# GPIO_SchematicMk2.net
KiCad netlist of a schematic drawn in EAGLE
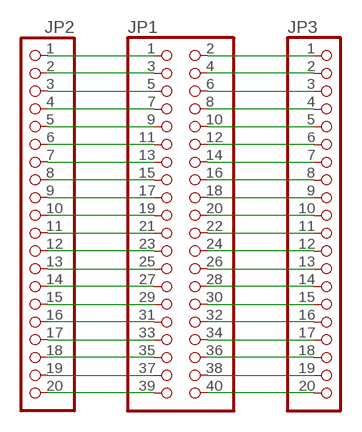
[diagram p0: schematic, sheet 1]

(export (version "E")
  (design (tool "Eeschema 10.0.6"))
  (components
    (comp (ref "JP1")
      (value "PINHD-2X20")
      (footprint "eagle-import:2X20")
      (libsource (lib "eagle-import") (part "PINHD-2X20"))
    )
    (comp (ref "JP2")
      (value "PINHD-1X20")
      (footprint "eagle-import:1X20")
      (libsource (lib "eagle-import") (part "PINHD-1X20"))
    )
    (comp (ref "JP3")
      (value "PINHD-1X20")
      (footprint "eagle-import:1X20")
      (libsource (lib "eagle-import") (part "PINHD-1X20"))
    )
  )
  (nets
    (net (code "1") (name "Net-(JP1-Pad1)") (class "Default")
      (node (ref "JP1") (pin "1") (pinfunction "1_1") (pintype "passive"))
      (node (ref "JP2") (pin "1") (pinfunction "1_1") (pintype "passive"))
    )
    (net (code "2") (name "Net-(JP1-Pad2)") (class "Default")
      (node (ref "JP1") (pin "2") (pinfunction "2_2") (pintype "passive"))
      (node (ref "JP3") (pin "1") (pinfunction "1_1") (pintype "passive"))
    )
    (net (code "3") (name "Net-(JP1-Pad3)") (class "Default")
      (node (ref "JP1") (pin "3") (pinfunction "3_3") (pintype "passive"))
      (node (ref "JP2") (pin "2") (pinfunction "2_2") (pintype "passive"))
    )
    (net (code "4") (name "Net-(JP1-Pad4)") (class "Default")
      (node (ref "JP1") (pin "4") (pinfunction "4_4") (pintype "passive"))
      (node (ref "JP3") (pin "2") (pinfunction "2_2") (pintype "passive"))
    )
    (net (code "5") (name "Net-(JP1-Pad5)") (class "Default")
      (node (ref "JP1") (pin "5") (pinfunction "5_5") (pintype "passive"))
      (node (ref "JP2") (pin "3") (pinfunction "3_3") (pintype "passive"))
    )
    (net (code "6") (name "Net-(JP1-Pad6)") (class "Default")
      (node (ref "JP1") (pin "6") (pinfunction "6_6") (pintype "passive"))
      (node (ref "JP3") (pin "3") (pinfunction "3_3") (pintype "passive"))
    )
    (net (code "7") (name "Net-(JP1-Pad7)") (class "Default")
      (node (ref "JP1") (pin "7") (pinfunction "7_7") (pintype "passive"))
      (node (ref "JP2") (pin "4") (pinfunction "4_4") (pintype "passive"))
    )
    (net (code "8") (name "Net-(JP1-Pad8)") (class "Default")
      (node (ref "JP1") (pin "8") (pinfunction "8_8") (pintype "passive"))
      (node (ref "JP3") (pin "4") (pinfunction "4_4") (pintype "passive"))
    )
    (net (code "9") (name "Net-(JP1-Pad9)") (class "Default")
      (node (ref "JP1") (pin "9") (pinfunction "9_9") (pintype "passive"))
      (node (ref "JP2") (pin "5") (pinfunction "5_5") (pintype "passive"))
    )
    (net (code "10") (name "Net-(JP1-Pad10)") (class "Default")
      (node (ref "JP1") (pin "10") (pinfunction "10_10") (pintype "passive"))
      (node (ref "JP3") (pin "5") (pinfunction "5_5") (pintype "passive"))
    )
    (net (code "11") (name "Net-(JP1-Pad11)") (class "Default")
      (node (ref "JP1") (pin "11") (pinfunction "11_11") (pintype "passive"))
      (node (ref "JP2") (pin "6") (pinfunction "6_6") (pintype "passive"))
    )
    (net (code "12") (name "Net-(JP1-Pad12)") (class "Default")
      (node (ref "JP1") (pin "12") (pinfunction "12_12") (pintype "passive"))
      (node (ref "JP3") (pin "6") (pinfunction "6_6") (pintype "passive"))
    )
    (net (code "13") (name "Net-(JP1-Pad13)") (class "Default")
      (node (ref "JP1") (pin "13") (pinfunction "13_13") (pintype "passive"))
      (node (ref "JP2") (pin "7") (pinfunction "7_7") (pintype "passive"))
    )
    (net (code "14") (name "Net-(JP1-Pad14)") (class "Default")
      (node (ref "JP1") (pin "14") (pinfunction "14_14") (pintype "passive"))
      (node (ref "JP3") (pin "7") (pinfunction "7_7") (pintype "passive"))
    )
    (net (code "15") (name "Net-(JP1-Pad15)") (class "Default")
      (node (ref "JP1") (pin "15") (pinfunction "15_15") (pintype "passive"))
      (node (ref "JP2") (pin "8") (pinfunction "8_8") (pintype "passive"))
    )
    (net (code "16") (name "Net-(JP1-Pad16)") (class "Default")
      (node (ref "JP1") (pin "16") (pinfunction "16_16") (pintype "passive"))
      (node (ref "JP3") (pin "8") (pinfunction "8_8") (pintype "passive"))
    )
    (net (code "17") (name "Net-(JP1-Pad17)") (class "Default")
      (node (ref "JP1") (pin "17") (pinfunction "17_17") (pintype "passive"))
      (node (ref "JP2") (pin "9") (pinfunction "9_9") (pintype "passive"))
    )
    (net (code "18") (name "Net-(JP1-Pad18)") (class "Default")
      (node (ref "JP1") (pin "18") (pinfunction "18_18") (pintype "passive"))
      (node (ref "JP3") (pin "9") (pinfunction "9_9") (pintype "passive"))
    )
    (net (code "19") (name "Net-(JP1-Pad19)") (class "Default")
      (node (ref "JP1") (pin "19") (pinfunction "19_19") (pintype "passive"))
      (node (ref "JP2") (pin "10") (pinfunction "10_10") (pintype "passive"))
    )
    (net (code "20") (name "Net-(JP1-Pad20)") (class "Default")
      (node (ref "JP1") (pin "20") (pinfunction "20_20") (pintype "passive"))
      (node (ref "JP3") (pin "10") (pinfunction "10_10") (pintype "passive"))
    )
    (net (code "21") (name "Net-(JP1-Pad21)") (class "Default")
      (node (ref "JP1") (pin "21") (pinfunction "21_21") (pintype "passive"))
      (node (ref "JP2") (pin "11") (pinfunction "11_11") (pintype "passive"))
    )
    (net (code "22") (name "Net-(JP1-Pad22)") (class "Default")
      (node (ref "JP1") (pin "22") (pinfunction "22_22") (pintype "passive"))
      (node (ref "JP3") (pin "11") (pinfunction "11_11") (pintype "passive"))
    )
    (net (code "23") (name "Net-(JP1-Pad23)") (class "Default")
      (node (ref "JP1") (pin "23") (pinfunction "23_23") (pintype "passive"))
      (node (ref "JP2") (pin "12") (pinfunction "12_12") (pintype "passive"))
    )
    (net (code "24") (name "Net-(JP1-Pad24)") (class "Default")
      (node (ref "JP1") (pin "24") (pinfunction "24_24") (pintype "passive"))
      (node (ref "JP3") (pin "12") (pinfunction "12_12") (pintype "passive"))
    )
    (net (code "25") (name "Net-(JP1-Pad25)") (class "Default")
      (node (ref "JP1") (pin "25") (pinfunction "25_25") (pintype "passive"))
      (node (ref "JP2") (pin "13") (pinfunction "13_13") (pintype "passive"))
    )
    (net (code "26") (name "Net-(JP1-Pad26)") (class "Default")
      (node (ref "JP1") (pin "26") (pinfunction "26_26") (pintype "passive"))
      (node (ref "JP3") (pin "13") (pinfunction "13_13") (pintype "passive"))
    )
    (net (code "27") (name "Net-(JP1-Pad27)") (class "Default")
      (node (ref "JP1") (pin "27") (pinfunction "27_27") (pintype "passive"))
      (node (ref "JP2") (pin "14") (pinfunction "14_14") (pintype "passive"))
    )
    (net (code "28") (name "Net-(JP1-Pad28)") (class "Default")
      (node (ref "JP1") (pin "28") (pinfunction "28_28") (pintype "passive"))
      (node (ref "JP3") (pin "14") (pinfunction "14_14") (pintype "passive"))
    )
    (net (code "29") (name "Net-(JP1-Pad29)") (class "Default")
      (node (ref "JP1") (pin "29") (pinfunction "29_29") (pintype "passive"))
      (node (ref "JP2") (pin "15") (pinfunction "15_15") (pintype "passive"))
    )
    (net (code "30") (name "Net-(JP1-Pad30)") (class "Default")
      (node (ref "JP1") (pin "30") (pinfunction "30_30") (pintype "passive"))
      (node (ref "JP3") (pin "15") (pinfunction "15_15") (pintype "passive"))
    )
    (net (code "31") (name "Net-(JP1-Pad31)") (class "Default")
      (node (ref "JP1") (pin "31") (pinfunction "31_31") (pintype "passive"))
      (node (ref "JP2") (pin "16") (pinfunction "16_16") (pintype "passive"))
    )
    (net (code "32") (name "Net-(JP1-Pad32)") (class "Default")
      (node (ref "JP1") (pin "32") (pinfunction "32_32") (pintype "passive"))
      (node (ref "JP3") (pin "16") (pinfunction "16_16") (pintype "passive"))
    )
    (net (code "33") (name "Net-(JP1-Pad33)") (class "Default")
      (node (ref "JP1") (pin "33") (pinfunction "33_33") (pintype "passive"))
      (node (ref "JP2") (pin "17") (pinfunction "17_17") (pintype "passive"))
    )
    (net (code "34") (name "Net-(JP1-Pad34)") (class "Default")
      (node (ref "JP1") (pin "34") (pinfunction "34_34") (pintype "passive"))
      (node (ref "JP3") (pin "17") (pinfunction "17_17") (pintype "passive"))
    )
    (net (code "35") (name "Net-(JP1-Pad35)") (class "Default")
      (node (ref "JP1") (pin "35") (pinfunction "35_35") (pintype "passive"))
      (node (ref "JP2") (pin "18") (pinfunction "18_18") (pintype "passive"))
    )
    (net (code "36") (name "Net-(JP1-Pad36)") (class "Default")
      (node (ref "JP1") (pin "36") (pinfunction "36_36") (pintype "passive"))
      (node (ref "JP3") (pin "18") (pinfunction "18_18") (pintype "passive"))
    )
    (net (code "37") (name "Net-(JP1-Pad37)") (class "Default")
      (node (ref "JP1") (pin "37") (pinfunction "37_37") (pintype "passive"))
      (node (ref "JP2") (pin "19") (pinfunction "19_19") (pintype "passive"))
    )
    (net (code "38") (name "Net-(JP1-Pad38)") (class "Default")
      (node (ref "JP1") (pin "38") (pinfunction "38_38") (pintype "passive"))
      (node (ref "JP3") (pin "19") (pinfunction "19_19") (pintype "passive"))
    )
    (net (code "39") (name "Net-(JP1-Pad39)") (class "Default")
      (node (ref "JP1") (pin "39") (pinfunction "39_39") (pintype "passive"))
      (node (ref "JP2") (pin "20") (pinfunction "20_20") (pintype "passive"))
    )
    (net (code "40") (name "Net-(JP1-Pad40)") (class "Default")
      (node (ref "JP1") (pin "40") (pinfunction "40_40") (pintype "passive"))
      (node (ref "JP3") (pin "20") (pinfunction "20_20") (pintype "passive"))
    )
  )
)
